# RS232_ttl.net
KiCad netlist of a schematic drawn in Altium Designer
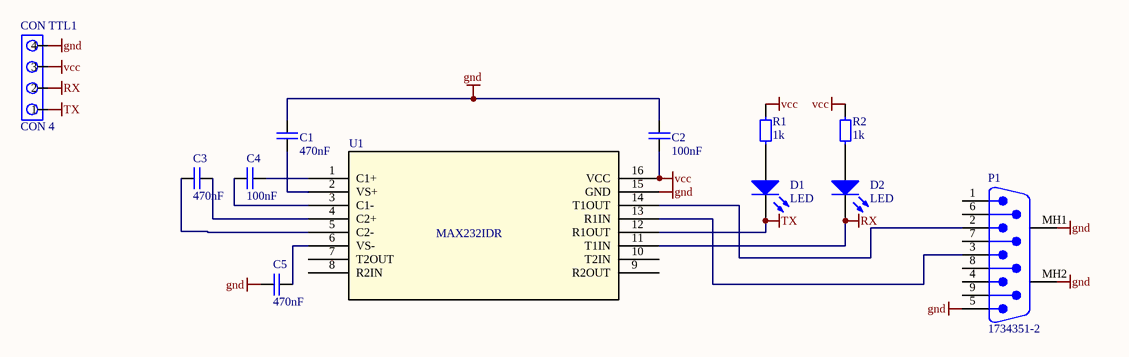
[diagram p0: RS232_ttl.SchDoc]

(export (version "E")
  (design (tool "Eeschema 10.0.6"))
  (components
    (comp (ref "C1")
      (value "470nF")
      (footprint "1206-C")
      (description "Capacitor")
      (fields (field (name "PUBLISHER") "Altium Limited"))
      (libsource (lib "SVV Library integrated") (part "Cap"))
    )
    (comp (ref "C2")
      (value "100nF")
      (footprint "1206-C")
      (description "Capacitor")
      (fields (field (name "PUBLISHER") "Altium Limited"))
      (libsource (lib "SVV Library integrated") (part "Cap"))
    )
    (comp (ref "C3")
      (value "470nF")
      (footprint "1206-C")
      (description "Capacitor")
      (fields (field (name "PUBLISHER") "Altium Limited"))
      (libsource (lib "SVV Library integrated") (part "Cap"))
    )
    (comp (ref "C4")
      (value "100nF")
      (footprint "1206-C")
      (description "Capacitor")
      (fields (field (name "PUBLISHER") "Altium Limited"))
      (libsource (lib "SVV Library integrated") (part "Cap"))
    )
    (comp (ref "C5")
      (value "470nF")
      (footprint "1206-C")
      (description "Capacitor")
      (fields (field (name "PUBLISHER") "Altium Limited"))
      (libsource (lib "SVV Library integrated") (part "Cap"))
    )
    (comp (ref "CON TTL1")
      (value "CON 4")
      (footprint "CON-4 2.54")
      (libsource (lib "SVV Library integrated") (part "CON 4"))
    )
    (comp (ref "D1")
      (value "LED")
      (footprint "1206-D")
      (description "Typical INFRARED GaAs LED")
      (fields (field (name "PUBLISHER") "Altium Limited"))
      (libsource (lib "SVV Library integrated") (part "LED"))
    )
    (comp (ref "D2")
      (value "LED")
      (footprint "1206-D")
      (description "Typical INFRARED GaAs LED")
      (fields (field (name "PUBLISHER") "Altium Limited"))
      (libsource (lib "SVV Library integrated") (part "LED"))
    )
    (comp (ref "P1")
      (value "1734351-2")
      (footprint "1734351-2")
      (fields (field (name "MANUFACTURER") "TE Connectivity"))
      (libsource (lib "Simulation Generic Components") (part "CN-2S-2M-D9"))
    )
    (comp (ref "R1")
      (value "1k")
      (footprint "1206-R")
      (libsource (lib "SVV Library integrated") (part "Res_2"))
    )
    (comp (ref "R2")
      (value "1k")
      (footprint "1206-R")
      (libsource (lib "SVV Library integrated") (part "Res_2"))
    )
    (comp (ref "U1")
      (value "MAX232IDR")
      (footprint "MAX232IDR")
      (description "No Description Available")
      (fields (field (name "COPYRIGHT") "Copyright (C) 2022 Ultra Librarian. All rights reserved."))
      (libsource (lib "MAX232IDR") (part "MAX232IDR"))
    )
  )
  (nets
    (net (code "1") (name "Net-(D1-A)") (class "Default")
      (node (ref "D1") (pin "1") (pinfunction "A_1") (pintype "passive"))
      (node (ref "R1") (pin "2") (pinfunction "2_2") (pintype "passive"))
    )
    (net (code "2") (name "Net-(D2-A)") (class "Default")
      (node (ref "D2") (pin "1") (pinfunction "A_1") (pintype "passive"))
      (node (ref "R2") (pin "2") (pinfunction "2_2") (pintype "passive"))
    )
    (net (code "3") (name "Net-(U1-C1+)") (class "Default")
      (node (ref "C4") (pin "2") (pinfunction "2_2") (pintype "passive"))
      (node (ref "U1") (pin "1") (pinfunction "C1+_1") (pintype "passive"))
    )
    (net (code "4") (name "Net-(U1-C1-)") (class "Default")
      (node (ref "C4") (pin "1") (pinfunction "1_1") (pintype "passive"))
      (node (ref "U1") (pin "3") (pinfunction "C1-_3") (pintype "passive"))
    )
    (net (code "5") (name "Net-(U1-C2+)") (class "Default")
      (node (ref "C3") (pin "2") (pinfunction "2_2") (pintype "passive"))
      (node (ref "U1") (pin "4") (pinfunction "C2+_4") (pintype "passive"))
    )
    (net (code "6") (name "Net-(U1-C2-)") (class "Default")
      (node (ref "C3") (pin "1") (pinfunction "1_1") (pintype "passive"))
      (node (ref "U1") (pin "5") (pinfunction "C2-_5") (pintype "passive"))
    )
    (net (code "7") (name "Net-(U1-R1IN)") (class "Default")
      (node (ref "P1") (pin "3") (pinfunction "3_3") (pintype "passive"))
      (node (ref "U1") (pin "13") (pinfunction "R1IN_13") (pintype "passive"))
    )
    (net (code "8") (name "Net-(U1-T1OUT)") (class "Default")
      (node (ref "P1") (pin "2") (pinfunction "2_2") (pintype "passive"))
      (node (ref "U1") (pin "14") (pinfunction "T1OUT_14") (pintype "passive"))
    )
    (net (code "9") (name "Net-(U1-VS+)") (class "Default")
      (node (ref "C1") (pin "1") (pinfunction "1_1") (pintype "passive"))
      (node (ref "U1") (pin "2") (pinfunction "VS+_2") (pintype "passive"))
    )
    (net (code "10") (name "Net-(U1-VS-)") (class "Default")
      (node (ref "C5") (pin "2") (pinfunction "2_2") (pintype "passive"))
      (node (ref "U1") (pin "6") (pinfunction "VS-_6") (pintype "passive"))
    )
    (net (code "11") (name "RX") (class "Default")
      (node (ref "CON TTL1") (pin "2") (pinfunction "2_2") (pintype "passive"))
      (node (ref "D2") (pin "2") (pinfunction "K_2") (pintype "passive"))
      (node (ref "U1") (pin "11") (pinfunction "T1IN_11") (pintype "passive"))
    )
    (net (code "12") (name "TX") (class "Default")
      (node (ref "CON TTL1") (pin "1") (pinfunction "1_1") (pintype "passive"))
      (node (ref "D1") (pin "2") (pinfunction "K_2") (pintype "passive"))
      (node (ref "U1") (pin "12") (pinfunction "R1OUT_12") (pintype "passive"))
    )
    (net (code "13") (name "gnd") (class "Default")
      (node (ref "C1") (pin "2") (pinfunction "2_2") (pintype "passive"))
      (node (ref "C2") (pin "2") (pinfunction "2_2") (pintype "passive"))
      (node (ref "C5") (pin "1") (pinfunction "1_1") (pintype "passive"))
      (node (ref "CON TTL1") (pin "4") (pinfunction "4_4") (pintype "passive"))
      (node (ref "P1") (pin "5") (pinfunction "5_5") (pintype "passive"))
      (node (ref "P1") (pin "MH1") (pinfunction "MH1_MH1") (pintype "passive"))
      (node (ref "P1") (pin "MH2") (pinfunction "MH2_MH2") (pintype "passive"))
      (node (ref "U1") (pin "15") (pinfunction "GND_15") (pintype "passive"))
    )
    (net (code "14") (name "unconnected-(P1-Pad1)") (class "Default")
      (node (ref "P1") (pin "1") (pinfunction "1_1") (pintype "passive"))
    )
    (net (code "15") (name "unconnected-(P1-Pad4)") (class "Default")
      (node (ref "P1") (pin "4") (pinfunction "4_4") (pintype "passive"))
    )
    (net (code "16") (name "unconnected-(P1-Pad6)") (class "Default")
      (node (ref "P1") (pin "6") (pinfunction "6_6") (pintype "passive"))
    )
    (net (code "17") (name "unconnected-(P1-Pad7)") (class "Default")
      (node (ref "P1") (pin "7") (pinfunction "7_7") (pintype "passive"))
    )
    (net (code "18") (name "unconnected-(P1-Pad8)") (class "Default")
      (node (ref "P1") (pin "8") (pinfunction "8_8") (pintype "passive"))
    )
    (net (code "19") (name "unconnected-(P1-Pad9)") (class "Default")
      (node (ref "P1") (pin "9") (pinfunction "9_9") (pintype "passive"))
    )
    (net (code "20") (name "unconnected-(U1-R2IN-Pad8)") (class "Default")
      (node (ref "U1") (pin "8") (pinfunction "R2IN_8") (pintype "passive"))
    )
    (net (code "21") (name "unconnected-(U1-R2OUT-Pad9)") (class "Default")
      (node (ref "U1") (pin "9") (pinfunction "R2OUT_9") (pintype "passive"))
    )
    (net (code "22") (name "unconnected-(U1-T2IN-Pad10)") (class "Default")
      (node (ref "U1") (pin "10") (pinfunction "T2IN_10") (pintype "passive"))
    )
    (net (code "23") (name "unconnected-(U1-T2OUT-Pad7)") (class "Default")
      (node (ref "U1") (pin "7") (pinfunction "T2OUT_7") (pintype "passive"))
    )
    (net (code "24") (name "vcc") (class "Default")
      (node (ref "C2") (pin "1") (pinfunction "1_1") (pintype "passive"))
      (node (ref "CON TTL1") (pin "3") (pinfunction "3_3") (pintype "passive"))
      (node (ref "R1") (pin "1") (pinfunction "1_1") (pintype "passive"))
      (node (ref "R2") (pin "1") (pinfunction "1_1") (pintype "passive"))
      (node (ref "U1") (pin "16") (pinfunction "VCC_16") (pintype "passive"))
    )
  )
)
